# ext_motor_M.net
KiCad netlist of a schematic drawn in EAGLE
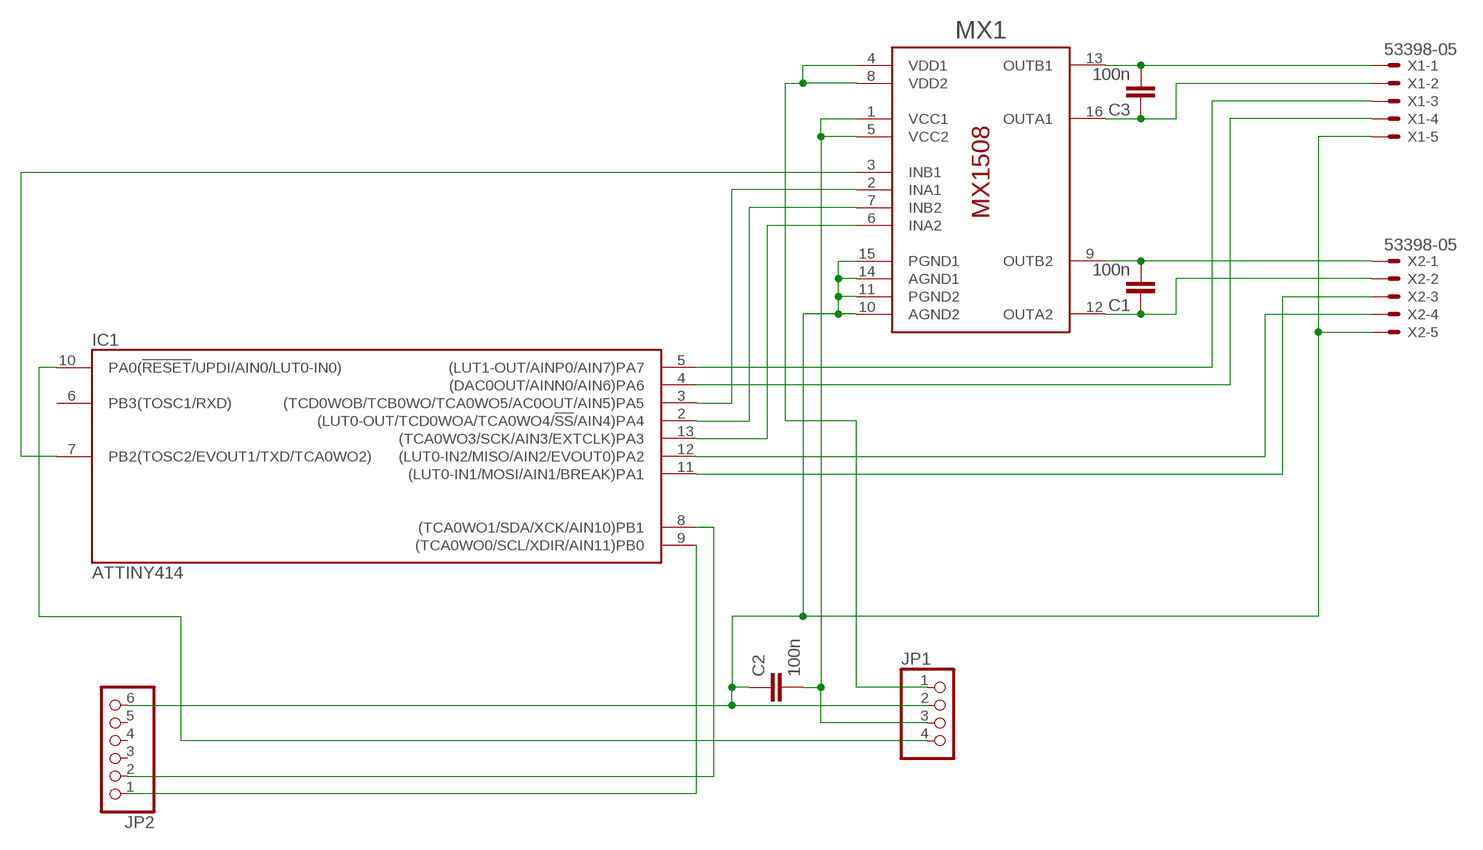
[diagram p0: schematic, sheet 1]

(export (version "E")
  (design (tool "Eeschema 10.0.6"))
  (components
    (comp (ref "C1")
      (value "100n")
      (footprint "eagle-import:C0805K")
      (libsource (lib "eagle-import") (part "C-EUC0805K"))
    )
    (comp (ref "C2")
      (value "100n")
      (footprint "eagle-import:C0805K")
      (libsource (lib "eagle-import") (part "C-EUC0805K"))
    )
    (comp (ref "C3")
      (value "100n")
      (footprint "eagle-import:C0805K")
      (libsource (lib "eagle-import") (part "C-EUC0805K"))
    )
    (comp (ref "IC1")
      (value "ATTINY414")
      (footprint "eagle-import:SO14")
      (libsource (lib "eagle-import") (part "ATTINY14-SSN4"))
    )
    (comp (ref "JP1")
      (value "PINHD-1X4")
      (footprint "eagle-import:1X04")
      (libsource (lib "eagle-import") (part "PINHD-1X4"))
    )
    (comp (ref "JP2")
      (value "PINHD-1X6")
      (footprint "eagle-import:1X06")
      (libsource (lib "eagle-import") (part "PINHD-1X6"))
    )
    (comp (ref "MX1")
      (value "MX1508")
      (footprint "eagle-import:SOP16")
      (libsource (lib "eagle-import") (part "MX1508"))
    )
    (comp (ref "X1")
      (value "53398-05")
      (footprint "eagle-import:53398-05")
      (fields (field (name "MF") "MOLEX"))
      (libsource (lib "eagle-import") (part "53?-05398"))
    )
    (comp (ref "X2")
      (value "53398-05")
      (footprint "eagle-import:53398-05")
      (fields (field (name "MF") "MOLEX"))
      (libsource (lib "eagle-import") (part "53?-05398"))
    )
  )
  (nets
    (net (code "1") (name "Net-(IC1A-(DAC0OUT{slash}AINN0{slash}AIN6)PA6)") (class "Default")
      (node (ref "IC1") (pin "4") (pinfunction "(DAC0OUT/AINN0/AIN6)PA6_4") (pintype "bidirectional"))
      (node (ref "X1") (pin "4") (pinfunction "S_4") (pintype "passive"))
    )
    (net (code "2") (name "Net-(IC1A-(LUT0-IN1{slash}MOSI{slash}AIN1{slash}BREAK)PA1)") (class "Default")
      (node (ref "IC1") (pin "11") (pinfunction "(LUT0-IN1/MOSI/AIN1/BREAK)PA1_11") (pintype "bidirectional"))
      (node (ref "X2") (pin "3") (pinfunction "S_3") (pintype "passive"))
    )
    (net (code "3") (name "Net-(IC1A-(LUT0-IN2{slash}MISO{slash}AIN2{slash}EVOUT0)PA2)") (class "Default")
      (node (ref "IC1") (pin "12") (pinfunction "(LUT0-IN2/MISO/AIN2/EVOUT0)PA2_12") (pintype "bidirectional"))
      (node (ref "X2") (pin "4") (pinfunction "S_4") (pintype "passive"))
    )
    (net (code "4") (name "Net-(IC1A-(LUT0-OUT{slash}TCD0WOA{slash}TCA0WO4{slash}~{SS}{slash}AIN4)PA4)") (class "Default")
      (node (ref "IC1") (pin "2") (pinfunction "(LUT0-OUT/TCD0WOA/TCA0WO4/~{SS}/AIN4)PA4_2") (pintype "bidirectional"))
      (node (ref "MX1") (pin "7") (pinfunction "INB2_7") (pintype "bidirectional"))
    )
    (net (code "5") (name "Net-(IC1A-(LUT1-OUT{slash}AINP0{slash}AIN7)PA7)") (class "Default")
      (node (ref "IC1") (pin "5") (pinfunction "(LUT1-OUT/AINP0/AIN7)PA7_5") (pintype "bidirectional"))
      (node (ref "X1") (pin "3") (pinfunction "S_3") (pintype "passive"))
    )
    (net (code "6") (name "Net-(IC1A-(TCA0WO0{slash}SCL{slash}XDIR{slash}AIN11)PB0)") (class "Default")
      (node (ref "IC1") (pin "9") (pinfunction "(TCA0WO0/SCL/XDIR/AIN11)PB0_9") (pintype "bidirectional"))
      (node (ref "JP2") (pin "1") (pinfunction "1_1") (pintype "passive"))
    )
    (net (code "7") (name "Net-(IC1A-(TCA0WO1{slash}SDA{slash}XCK{slash}AIN10)PB1)") (class "Default")
      (node (ref "IC1") (pin "8") (pinfunction "(TCA0WO1/SDA/XCK/AIN10)PB1_8") (pintype "bidirectional"))
      (node (ref "JP2") (pin "2") (pinfunction "2_2") (pintype "passive"))
    )
    (net (code "8") (name "Net-(IC1A-(TCA0WO3{slash}SCK{slash}AIN3{slash}EXTCLK)PA3)") (class "Default")
      (node (ref "IC1") (pin "13") (pinfunction "(TCA0WO3/SCK/AIN3/EXTCLK)PA3_13") (pintype "bidirectional"))
      (node (ref "MX1") (pin "6") (pinfunction "INA2_6") (pintype "bidirectional"))
    )
    (net (code "9") (name "Net-(IC1A-(TCD0WOB{slash}TCB0WO{slash}TCA0WO5{slash}AC0OUT{slash}AIN5)PA5)") (class "Default")
      (node (ref "IC1") (pin "3") (pinfunction "(TCD0WOB/TCB0WO/TCA0WO5/AC0OUT/AIN5)PA5_3") (pintype "bidirectional"))
      (node (ref "MX1") (pin "2") (pinfunction "INA1_2") (pintype "bidirectional"))
    )
    (net (code "10") (name "Net-(IC1A-PA0(~{RESET}{slash}UPDI{slash}AIN0{slash}LUT0-IN0))") (class "Default")
      (node (ref "IC1") (pin "10") (pinfunction "PA0(~{RESET}/UPDI/AIN0/LUT0-IN0)_10") (pintype "bidirectional"))
      (node (ref "JP1") (pin "4") (pinfunction "4_4") (pintype "passive"))
    )
    (net (code "11") (name "Net-(IC1A-PB2(TOSC2{slash}EVOUT1{slash}TXD{slash}TCA0WO2))") (class "Default")
      (node (ref "IC1") (pin "7") (pinfunction "PB2(TOSC2/EVOUT1/TXD/TCA0WO2)_7") (pintype "bidirectional"))
      (node (ref "MX1") (pin "3") (pinfunction "INB1_3") (pintype "bidirectional"))
    )
    (net (code "12") (name "Net-(MX1-AGND1)") (class "Default")
      (node (ref "C2") (pin "1") (pinfunction "1_1") (pintype "passive"))
      (node (ref "JP1") (pin "2") (pinfunction "2_2") (pintype "passive"))
      (node (ref "JP2") (pin "6") (pinfunction "6_6") (pintype "passive"))
      (node (ref "MX1") (pin "10") (pinfunction "AGND2_10") (pintype "bidirectional"))
      (node (ref "MX1") (pin "11") (pinfunction "PGND2_11") (pintype "bidirectional"))
      (node (ref "MX1") (pin "14") (pinfunction "AGND1_14") (pintype "bidirectional"))
      (node (ref "MX1") (pin "15") (pinfunction "PGND1_15") (pintype "bidirectional"))
      (node (ref "X1") (pin "5") (pinfunction "S_5") (pintype "passive"))
      (node (ref "X2") (pin "5") (pinfunction "S_5") (pintype "passive"))
    )
    (net (code "13") (name "Net-(MX1-OUTA1)") (class "Default")
      (node (ref "C3") (pin "1") (pinfunction "1_1") (pintype "passive"))
      (node (ref "MX1") (pin "16") (pinfunction "OUTA1_16") (pintype "bidirectional"))
      (node (ref "X1") (pin "2") (pinfunction "S_2") (pintype "passive"))
    )
    (net (code "14") (name "Net-(MX1-OUTA2)") (class "Default")
      (node (ref "C1") (pin "1") (pinfunction "1_1") (pintype "passive"))
      (node (ref "MX1") (pin "12") (pinfunction "OUTA2_12") (pintype "bidirectional"))
      (node (ref "X2") (pin "2") (pinfunction "S_2") (pintype "passive"))
    )
    (net (code "15") (name "Net-(MX1-OUTB1)") (class "Default")
      (node (ref "C3") (pin "2") (pinfunction "2_2") (pintype "passive"))
      (node (ref "MX1") (pin "13") (pinfunction "OUTB1_13") (pintype "bidirectional"))
      (node (ref "X1") (pin "1") (pinfunction "S_1") (pintype "passive"))
    )
    (net (code "16") (name "Net-(MX1-OUTB2)") (class "Default")
      (node (ref "C1") (pin "2") (pinfunction "2_2") (pintype "passive"))
      (node (ref "MX1") (pin "9") (pinfunction "OUTB2_9") (pintype "bidirectional"))
      (node (ref "X2") (pin "1") (pinfunction "S_1") (pintype "passive"))
    )
    (net (code "17") (name "Net-(MX1-VCC1)") (class "Default")
      (node (ref "C2") (pin "2") (pinfunction "2_2") (pintype "passive"))
      (node (ref "JP1") (pin "3") (pinfunction "3_3") (pintype "passive"))
      (node (ref "MX1") (pin "1") (pinfunction "VCC1_1") (pintype "bidirectional"))
      (node (ref "MX1") (pin "5") (pinfunction "VCC2_5") (pintype "bidirectional"))
    )
    (net (code "18") (name "Net-(MX1-VDD1)") (class "Default")
      (node (ref "JP1") (pin "1") (pinfunction "1_1") (pintype "passive"))
      (node (ref "MX1") (pin "4") (pinfunction "VDD1_4") (pintype "bidirectional"))
      (node (ref "MX1") (pin "8") (pinfunction "VDD2_8") (pintype "bidirectional"))
    )
    (net (code "19") (name "unconnected-(IC1A-PB3(TOSC1{slash}RXD)-Pad6)") (class "Default")
      (node (ref "IC1") (pin "6") (pinfunction "PB3(TOSC1/RXD)_6") (pintype "bidirectional"))
    )
    (net (code "20") (name "unconnected-(JP2-Pad3)") (class "Default")
      (node (ref "JP2") (pin "3") (pinfunction "3_3") (pintype "passive"))
    )
    (net (code "21") (name "unconnected-(JP2-Pad4)") (class "Default")
      (node (ref "JP2") (pin "4") (pinfunction "4_4") (pintype "passive"))
    )
    (net (code "22") (name "unconnected-(JP2-Pad5)") (class "Default")
      (node (ref "JP2") (pin "5") (pinfunction "5_5") (pintype "passive"))
    )
  )
)
